# MCU.net
KiCad netlist of a schematic drawn in Altium Designer
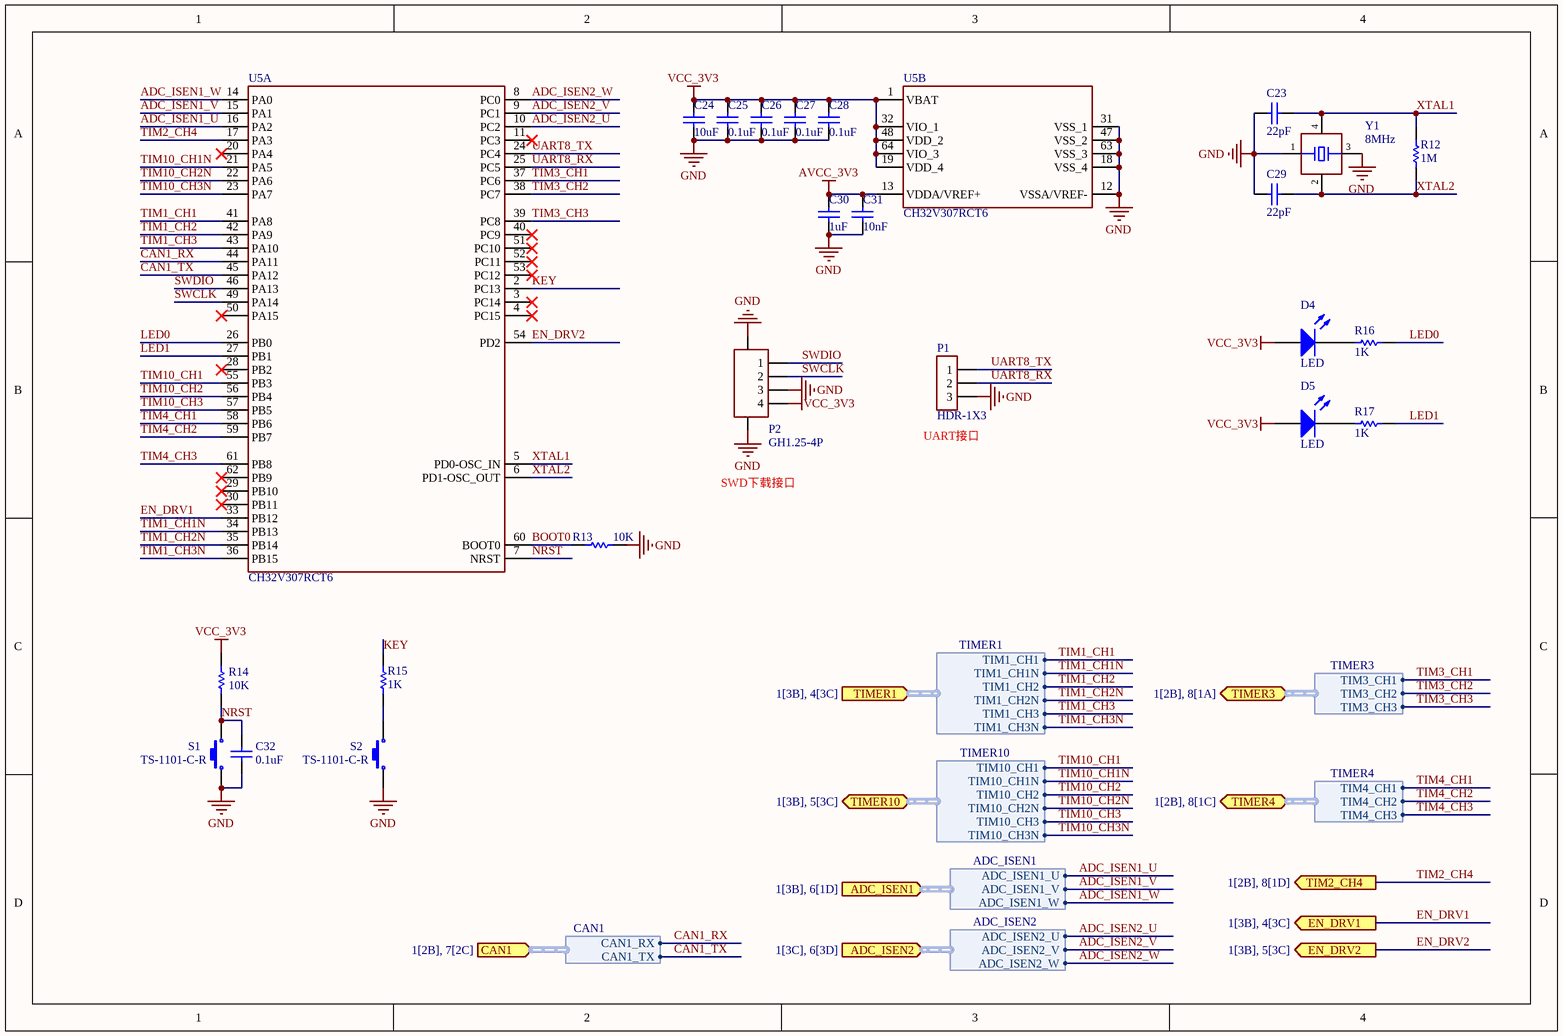
[diagram p0: MCU.SchDoc]

(export (version "E")
  (design (tool "Eeschema 10.0.6"))
  (components
    (comp (ref "C23")
      (value "22pF")
      (footprint "C0603_NS")
      (description "Capacitor")
      (fields (field (name "PUBLISHER") "Altium Limited"))
      (libsource (lib "Miscellaneous Devices") (part "Cap"))
    )
    (comp (ref "C24")
      (value "10uF")
      (footprint "C0603_NS")
      (description "Capacitor")
      (libsource (lib "Miscellaneous Devices") (part "Cap"))
    )
    (comp (ref "C25")
      (value "0.1uF")
      (footprint "C0603_NS")
      (description "Capacitor")
      (libsource (lib "Miscellaneous Devices") (part "Cap"))
    )
    (comp (ref "C26")
      (value "0.1uF")
      (footprint "C0603_NS")
      (description "Capacitor")
      (libsource (lib "Miscellaneous Devices") (part "Cap"))
    )
    (comp (ref "C27")
      (value "0.1uF")
      (footprint "C0603_NS")
      (description "Capacitor")
      (libsource (lib "Miscellaneous Devices") (part "Cap"))
    )
    (comp (ref "C28")
      (value "0.1uF")
      (footprint "C0603_NS")
      (description "Capacitor")
      (libsource (lib "Miscellaneous Devices") (part "Cap"))
    )
    (comp (ref "C29")
      (value "22pF")
      (footprint "C0603_NS")
      (description "Capacitor")
      (fields (field (name "PUBLISHER") "Altium Limited"))
      (libsource (lib "Miscellaneous Devices") (part "Cap"))
    )
    (comp (ref "C30")
      (value "1uF")
      (footprint "C0603_NS")
      (description "Capacitor")
      (libsource (lib "Miscellaneous Devices") (part "Cap"))
    )
    (comp (ref "C31")
      (value "10nF")
      (footprint "C0603_NS")
      (description "Capacitor")
      (libsource (lib "Miscellaneous Devices") (part "Cap"))
    )
    (comp (ref "C32")
      (value "0.1uF")
      (footprint "C0603_NS")
      (description "Capacitor")
      (libsource (lib "Miscellaneous Devices") (part "Cap"))
    )
    (comp (ref "D4")
      (value "LED")
      (footprint "LED0603_NS")
      (description "Typical INFRARED GaAs LED")
      (libsource (lib "Miscellaneous Devices") (part "LED0"))
    )
    (comp (ref "D5")
      (value "LED")
      (footprint "LED0603_NS")
      (description "Typical INFRARED GaAs LED")
      (libsource (lib "Miscellaneous Devices") (part "LED0"))
    )
    (comp (ref "P1")
      (value "HDR-1X3")
      (footprint "HDR2.54-WI-3P")
      (libsource (lib "my_library") (part "HDR-1X3"))
    )
    (comp (ref "P2")
      (value "GH1.25-4P")
      (footprint "A1257WR-S-4P")
      (libsource (lib "my_library") (part "Header4"))
    )
    (comp (ref "R12")
      (value "1M")
      (footprint "R0603_NS")
      (description "Resistor")
      (libsource (lib "Miscellaneous Devices") (part "Res1"))
    )
    (comp (ref "R13")
      (value "10K")
      (footprint "R0603_NS")
      (description "Resistor")
      (libsource (lib "Miscellaneous Devices") (part "Res1"))
    )
    (comp (ref "R14")
      (value "10K")
      (footprint "R0603_NS")
      (description "Resistor")
      (libsource (lib "Miscellaneous Devices") (part "Res1"))
    )
    (comp (ref "R15")
      (value "1K")
      (footprint "R0603_NS")
      (description "Resistor")
      (libsource (lib "Miscellaneous Devices") (part "Res1"))
    )
    (comp (ref "R16")
      (value "1K")
      (footprint "R0603_NS")
      (description "Resistor")
      (libsource (lib "Miscellaneous Devices") (part "Res1"))
    )
    (comp (ref "R17")
      (value "1K")
      (footprint "R0603_NS")
      (description "Resistor")
      (libsource (lib "Miscellaneous Devices") (part "Res1"))
    )
    (comp (ref "S1") (value "TS-1101-C-R") (footprint "TS-1101") (libsource (lib "my_library") (part "SW")))
    (comp (ref "S2") (value "TS-1101-C-R") (footprint "TS-1101") (libsource (lib "my_library") (part "SW")))
    (comp (ref "U5")
      (value "CH32V307RCT6")
      (footprint "LQFP64_N")
      (libsource (lib "my_library") (part "CH32V307RCT6"))
    )
    (comp (ref "Y1") (value "8MHz") (footprint "SMD-3225-4P") (libsource (lib "my_library") (part "XTAL")))
  )
  (nets
    (net (code "8") (name "/ADC_ISEN1_U") (class "Default")
      (node (ref "U5") (pin "16") (pinfunction "PA2_16") (pintype "passive"))
    )
    (net (code "9") (name "/ADC_ISEN1_V") (class "Default")
      (node (ref "U5") (pin "15") (pinfunction "PA1_15") (pintype "passive"))
    )
    (net (code "10") (name "/ADC_ISEN1_W") (class "Default")
      (node (ref "U5") (pin "14") (pinfunction "PA0_14") (pintype "passive"))
    )
    (net (code "11") (name "/ADC_ISEN2_U") (class "Default")
      (node (ref "U5") (pin "10") (pinfunction "PC2_10") (pintype "passive"))
    )
    (net (code "12") (name "/ADC_ISEN2_V") (class "Default")
      (node (ref "U5") (pin "9") (pinfunction "PC1_9") (pintype "passive"))
    )
    (net (code "13") (name "/ADC_ISEN2_W") (class "Default")
      (node (ref "U5") (pin "8") (pinfunction "PC0_8") (pintype "passive"))
    )
    (net (code "14") (name "/BOOT0") (class "Default")
      (node (ref "R13") (pin "1") (pinfunction "1_1") (pintype "passive"))
      (node (ref "U5") (pin "60") (pinfunction "BOOT0_60") (pintype "passive"))
    )
    (net (code "15") (name "/CAN1_RX") (class "Default")
      (node (ref "U5") (pin "44") (pinfunction "PA11_44") (pintype "passive"))
    )
    (net (code "16") (name "/CAN1_TX") (class "Default")
      (node (ref "U5") (pin "45") (pinfunction "PA12_45") (pintype "passive"))
    )
    (net (code "17") (name "/EN_DRV1") (class "Default")
      (node (ref "U5") (pin "33") (pinfunction "PB12_33") (pintype "passive"))
    )
    (net (code "18") (name "/EN_DRV2") (class "Default")
      (node (ref "U5") (pin "54") (pinfunction "PD2_54") (pintype "passive"))
    )
    (net (code "19") (name "/KEY") (class "Default")
      (node (ref "R15") (pin "2") (pinfunction "2_2") (pintype "passive"))
      (node (ref "U5") (pin "2") (pinfunction "PC13_2") (pintype "passive"))
    )
    (net (code "20") (name "/LED0") (class "Default")
      (node (ref "R16") (pin "2") (pinfunction "2_2") (pintype "passive"))
      (node (ref "U5") (pin "26") (pinfunction "PB0_26") (pintype "passive"))
    )
    (net (code "21") (name "/LED1") (class "Default")
      (node (ref "R17") (pin "2") (pinfunction "2_2") (pintype "passive"))
      (node (ref "U5") (pin "27") (pinfunction "PB1_27") (pintype "passive"))
    )
    (net (code "22") (name "/NRST") (class "Default")
      (node (ref "C32") (pin "2") (pinfunction "2_2") (pintype "passive"))
      (node (ref "R14") (pin "2") (pinfunction "2_2") (pintype "passive"))
      (node (ref "S1") (pin "2") (pinfunction "2_2") (pintype "passive"))
      (node (ref "U5") (pin "7") (pinfunction "NRST_7") (pintype "passive"))
    )
    (net (code "23") (name "/SWCLK") (class "Default")
      (node (ref "P2") (pin "2") (pinfunction "2_2") (pintype "passive"))
      (node (ref "U5") (pin "49") (pinfunction "PA14_49") (pintype "passive"))
    )
    (net (code "24") (name "/SWDIO") (class "Default")
      (node (ref "P2") (pin "1") (pinfunction "1_1") (pintype "passive"))
      (node (ref "U5") (pin "46") (pinfunction "PA13_46") (pintype "passive"))
    )
    (net (code "25") (name "/TIM1_CH1") (class "Default")
      (node (ref "U5") (pin "41") (pinfunction "PA8_41") (pintype "passive"))
    )
    (net (code "26") (name "/TIM1_CH1N") (class "Default")
      (node (ref "U5") (pin "34") (pinfunction "PB13_34") (pintype "passive"))
    )
    (net (code "27") (name "/TIM1_CH2") (class "Default")
      (node (ref "U5") (pin "42") (pinfunction "PA9_42") (pintype "passive"))
    )
    (net (code "28") (name "/TIM1_CH2N") (class "Default")
      (node (ref "U5") (pin "35") (pinfunction "PB14_35") (pintype "passive"))
    )
    (net (code "29") (name "/TIM1_CH3") (class "Default")
      (node (ref "U5") (pin "43") (pinfunction "PA10_43") (pintype "passive"))
    )
    (net (code "30") (name "/TIM1_CH3N") (class "Default")
      (node (ref "U5") (pin "36") (pinfunction "PB15_36") (pintype "passive"))
    )
    (net (code "31") (name "/TIM2_CH4") (class "Default")
      (node (ref "U5") (pin "17") (pinfunction "PA3_17") (pintype "passive"))
    )
    (net (code "32") (name "/TIM3_CH1") (class "Default")
      (node (ref "U5") (pin "37") (pinfunction "PC6_37") (pintype "passive"))
    )
    (net (code "33") (name "/TIM3_CH2") (class "Default")
      (node (ref "U5") (pin "38") (pinfunction "PC7_38") (pintype "passive"))
    )
    (net (code "34") (name "/TIM3_CH3") (class "Default")
      (node (ref "U5") (pin "39") (pinfunction "PC8_39") (pintype "passive"))
    )
    (net (code "35") (name "/TIM4_CH1") (class "Default")
      (node (ref "U5") (pin "58") (pinfunction "PB6_58") (pintype "passive"))
    )
    (net (code "36") (name "/TIM4_CH2") (class "Default")
      (node (ref "U5") (pin "59") (pinfunction "PB7_59") (pintype "passive"))
    )
    (net (code "37") (name "/TIM4_CH3") (class "Default")
      (node (ref "U5") (pin "61") (pinfunction "PB8_61") (pintype "passive"))
    )
    (net (code "38") (name "/TIM10_CH1") (class "Default")
      (node (ref "U5") (pin "55") (pinfunction "PB3_55") (pintype "passive"))
    )
    (net (code "39") (name "/TIM10_CH1N") (class "Default")
      (node (ref "U5") (pin "21") (pinfunction "PA5_21") (pintype "passive"))
    )
    (net (code "40") (name "/TIM10_CH2") (class "Default")
      (node (ref "U5") (pin "56") (pinfunction "PB4_56") (pintype "passive"))
    )
    (net (code "41") (name "/TIM10_CH2N") (class "Default")
      (node (ref "U5") (pin "22") (pinfunction "PA6_22") (pintype "passive"))
    )
    (net (code "42") (name "/TIM10_CH3") (class "Default")
      (node (ref "U5") (pin "57") (pinfunction "PB5_57") (pintype "passive"))
    )
    (net (code "43") (name "/TIM10_CH3N") (class "Default")
      (node (ref "U5") (pin "23") (pinfunction "PA7_23") (pintype "passive"))
    )
    (net (code "44") (name "/UART8_RX") (class "Default")
      (node (ref "P1") (pin "2") (pinfunction "2_2") (pintype "passive"))
      (node (ref "U5") (pin "25") (pinfunction "PC5_25") (pintype "passive"))
    )
    (net (code "45") (name "/UART8_TX") (class "Default")
      (node (ref "P1") (pin "1") (pinfunction "1_1") (pintype "passive"))
      (node (ref "U5") (pin "24") (pinfunction "PC4_24") (pintype "passive"))
    )
    (net (code "46") (name "/XTAL1") (class "Default")
      (node (ref "C23") (pin "2") (pinfunction "2_2") (pintype "passive"))
      (node (ref "R12") (pin "2") (pinfunction "2_2") (pintype "passive"))
      (node (ref "U5") (pin "5") (pinfunction "PD0-OSC_IN_5") (pintype "passive"))
      (node (ref "Y1") (pin "4") (pinfunction "4_4") (pintype "passive"))
    )
    (net (code "47") (name "/XTAL2") (class "Default")
      (node (ref "C29") (pin "2") (pinfunction "2_2") (pintype "passive"))
      (node (ref "R12") (pin "1") (pinfunction "1_1") (pintype "passive"))
      (node (ref "U5") (pin "6") (pinfunction "PD1-OSC_OUT_6") (pintype "passive"))
      (node (ref "Y1") (pin "2") (pinfunction "2_2") (pintype "passive"))
    )
    (net (code "55") (name "AVCC_3V3") (class "Default")
      (node (ref "C30") (pin "2") (pinfunction "2_2") (pintype "passive"))
      (node (ref "C31") (pin "2") (pinfunction "2_2") (pintype "passive"))
      (node (ref "U5") (pin "13") (pinfunction "VDDA/VREF+_13") (pintype "power_in"))
    )
    (net (code "56") (name "GND") (class "Default")
      (node (ref "C23") (pin "1") (pinfunction "1_1") (pintype "passive"))
      (node (ref "C24") (pin "1") (pinfunction "1_1") (pintype "passive"))
      (node (ref "C25") (pin "1") (pinfunction "1_1") (pintype "passive"))
      (node (ref "C26") (pin "1") (pinfunction "1_1") (pintype "passive"))
      (node (ref "C27") (pin "1") (pinfunction "1_1") (pintype "passive"))
      (node (ref "C28") (pin "1") (pinfunction "1_1") (pintype "passive"))
      (node (ref "C29") (pin "1") (pinfunction "1_1") (pintype "passive"))
      (node (ref "C30") (pin "1") (pinfunction "1_1") (pintype "passive"))
      (node (ref "C31") (pin "1") (pinfunction "1_1") (pintype "passive"))
      (node (ref "C32") (pin "1") (pinfunction "1_1") (pintype "passive"))
      (node (ref "P1") (pin "3") (pinfunction "3_3") (pintype "passive"))
      (node (ref "P2") (pin "0") (pinfunction "0_0") (pintype "passive"))
      (node (ref "P2") (pin "3") (pinfunction "3_3") (pintype "passive"))
      (node (ref "R13") (pin "2") (pinfunction "2_2") (pintype "passive"))
      (node (ref "S1") (pin "1") (pinfunction "1_1") (pintype "passive"))
      (node (ref "S2") (pin "1") (pinfunction "1_1") (pintype "passive"))
      (node (ref "U5") (pin "12") (pinfunction "VSSA/VREF-_12") (pintype "power_in"))
      (node (ref "U5") (pin "18") (pinfunction "VSS_4_18") (pintype "power_in"))
      (node (ref "U5") (pin "31") (pinfunction "VSS_1_31") (pintype "power_in"))
      (node (ref "U5") (pin "47") (pinfunction "VSS_2_47") (pintype "power_in"))
      (node (ref "U5") (pin "63") (pinfunction "VSS_3_63") (pintype "power_in"))
      (node (ref "Y1") (pin "1") (pinfunction "1_1") (pintype "passive"))
      (node (ref "Y1") (pin "3") (pinfunction "3_3") (pintype "passive"))
    )
    (net (code "57") (name "Net-(D4-K)") (class "Default")
      (node (ref "D4") (pin "2") (pinfunction "K_2") (pintype "passive"))
      (node (ref "R16") (pin "1") (pinfunction "1_1") (pintype "passive"))
    )
    (net (code "58") (name "Net-(D5-K)") (class "Default")
      (node (ref "D5") (pin "2") (pinfunction "K_2") (pintype "passive"))
      (node (ref "R17") (pin "1") (pinfunction "1_1") (pintype "passive"))
    )
    (net (code "59") (name "Net-(R15-Pad1)") (class "Default")
      (node (ref "R15") (pin "1") (pinfunction "1_1") (pintype "passive"))
      (node (ref "S2") (pin "2") (pinfunction "2_2") (pintype "passive"))
    )
    (net (code "60") (name "VCC_3V3") (class "Default")
      (node (ref "C24") (pin "2") (pinfunction "2_2") (pintype "passive"))
      (node (ref "C25") (pin "2") (pinfunction "2_2") (pintype "passive"))
      (node (ref "C26") (pin "2") (pinfunction "2_2") (pintype "passive"))
      (node (ref "C27") (pin "2") (pinfunction "2_2") (pintype "passive"))
      (node (ref "C28") (pin "2") (pinfunction "2_2") (pintype "passive"))
      (node (ref "D4") (pin "1") (pinfunction "A_1") (pintype "passive"))
      (node (ref "D5") (pin "1") (pinfunction "A_1") (pintype "passive"))
      (node (ref "P2") (pin "4") (pinfunction "4_4") (pintype "passive"))
      (node (ref "R14") (pin "1") (pinfunction "1_1") (pintype "passive"))
      (node (ref "U5") (pin "1") (pinfunction "VBAT_1") (pintype "power_in"))
      (node (ref "U5") (pin "19") (pinfunction "VDD_4_19") (pintype "power_in"))
      (node (ref "U5") (pin "32") (pinfunction "VIO_1_32") (pintype "power_in"))
      (node (ref "U5") (pin "48") (pinfunction "VDD_2_48") (pintype "power_in"))
      (node (ref "U5") (pin "64") (pinfunction "VIO_3_64") (pintype "power_in"))
    )
    (net (code "61") (name "unconnected-(U5A-PA4-Pad20)") (class "Default")
      (node (ref "U5") (pin "20") (pinfunction "PA4_20") (pintype "passive+no_connect"))
    )
    (net (code "62") (name "unconnected-(U5A-PA15-Pad50)") (class "Default")
      (node (ref "U5") (pin "50") (pinfunction "PA15_50") (pintype "passive+no_connect"))
    )
    (net (code "63") (name "unconnected-(U5A-PB2-Pad28)") (class "Default")
      (node (ref "U5") (pin "28") (pinfunction "PB2_28") (pintype "passive+no_connect"))
    )
    (net (code "64") (name "unconnected-(U5A-PB9-Pad62)") (class "Default")
      (node (ref "U5") (pin "62") (pinfunction "PB9_62") (pintype "passive+no_connect"))
    )
    (net (code "65") (name "unconnected-(U5A-PB10-Pad29)") (class "Default")
      (node (ref "U5") (pin "29") (pinfunction "PB10_29") (pintype "passive+no_connect"))
    )
    (net (code "66") (name "unconnected-(U5A-PB11-Pad30)") (class "Default")
      (node (ref "U5") (pin "30") (pinfunction "PB11_30") (pintype "passive+no_connect"))
    )
    (net (code "67") (name "unconnected-(U5A-PC3-Pad11)") (class "Default")
      (node (ref "U5") (pin "11") (pinfunction "PC3_11") (pintype "passive+no_connect"))
    )
    (net (code "68") (name "unconnected-(U5A-PC9-Pad40)") (class "Default")
      (node (ref "U5") (pin "40") (pinfunction "PC9_40") (pintype "passive+no_connect"))
    )
    (net (code "69") (name "unconnected-(U5A-PC10-Pad51)") (class "Default")
      (node (ref "U5") (pin "51") (pinfunction "PC10_51") (pintype "passive+no_connect"))
    )
    (net (code "70") (name "unconnected-(U5A-PC11-Pad52)") (class "Default")
      (node (ref "U5") (pin "52") (pinfunction "PC11_52") (pintype "passive+no_connect"))
    )
    (net (code "71") (name "unconnected-(U5A-PC12-Pad53)") (class "Default")
      (node (ref "U5") (pin "53") (pinfunction "PC12_53") (pintype "passive+no_connect"))
    )
    (net (code "72") (name "unconnected-(U5A-PC14-Pad3)") (class "Default")
      (node (ref "U5") (pin "3") (pinfunction "PC14_3") (pintype "passive+no_connect"))
    )
    (net (code "73") (name "unconnected-(U5A-PC15-Pad4)") (class "Default")
      (node (ref "U5") (pin "4") (pinfunction "PC15_4") (pintype "passive+no_connect"))
    )
  )
)
